# Ant-v1.net
KiCad netlist of a schematic drawn in EAGLE
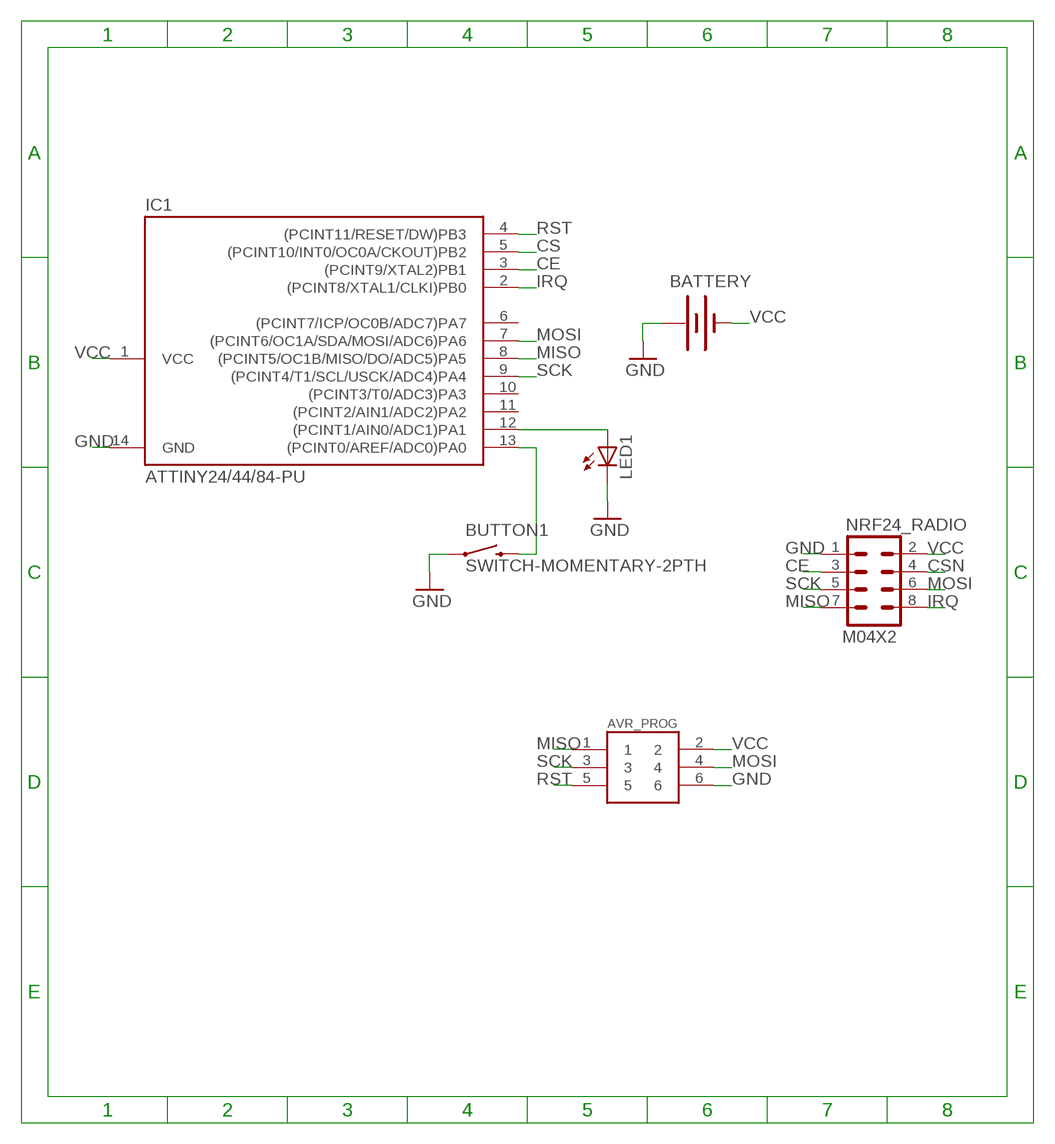
[diagram p0: schematic, sheet 1]

(export (version "E")
  (design (tool "Eeschema 10.0.6"))
  (components
    (comp (ref "AVR_PROG")
      (value "M03X2")
      (footprint "eagle-import:2X3-SHROUDED")
      (libsource (lib "eagle-import") (part "M03X2"))
    )
    (comp (ref "BATTERY")
      (value "BATTERY20PTH")
      (footprint "eagle-import:BATTCOM_20MM_PTH")
      (libsource (lib "eagle-import") (part "BATTERY20PTH"))
    )
    (comp (ref "BUTTON1")
      (value "SWITCH-MOMENTARY-2PTH")
      (footprint "eagle-import:TACTILE-PTH")
      (libsource (lib "eagle-import") (part "SWITCH-MOMENTARY-2PTH"))
    )
    (comp (ref "IC1")
      (value "ATTINY24/44/84-PU")
      (footprint "eagle-import:DIL14")
      (libsource (lib "eagle-import") (part "ATTINY24/44/84-PU"))
    )
    (comp (ref "LED1")
      (value "LED3MM")
      (footprint "eagle-import:LED3MM")
      (libsource (lib "eagle-import") (part "LED3MM"))
    )
    (comp (ref "NRF24_RADIO")
      (value "M04X2")
      (footprint "eagle-import:2X4")
      (libsource (lib "eagle-import") (part "M04X2"))
    )
  )
  (nets
    (net (code "1") (name "/CE") (class "Default")
      (node (ref "IC1") (pin "3") (pinfunction "(PCINT9/XTAL2)PB1_3") (pintype "bidirectional"))
      (node (ref "NRF24_RADIO") (pin "3") (pinfunction "3_3") (pintype "passive"))
    )
    (net (code "2") (name "/CS") (class "Default")
      (node (ref "IC1") (pin "5") (pinfunction "(PCINT10/INT0/OC0A/CKOUT)PB2_5") (pintype "bidirectional"))
    )
    (net (code "3") (name "/CSN") (class "Default")
      (node (ref "NRF24_RADIO") (pin "4") (pinfunction "4_4") (pintype "passive"))
    )
    (net (code "4") (name "/IRQ") (class "Default")
      (node (ref "IC1") (pin "2") (pinfunction "(PCINT8/XTAL1/CLKI)PB0_2") (pintype "bidirectional"))
      (node (ref "NRF24_RADIO") (pin "8") (pinfunction "8_8") (pintype "passive"))
    )
    (net (code "5") (name "/MISO") (class "Default")
      (node (ref "AVR_PROG") (pin "1") (pinfunction "1_1") (pintype "bidirectional"))
      (node (ref "IC1") (pin "8") (pinfunction "(PCINT5/OC1B/MISO/DO/ADC5)PA5_8") (pintype "bidirectional"))
      (node (ref "NRF24_RADIO") (pin "7") (pinfunction "7_7") (pintype "passive"))
    )
    (net (code "6") (name "/MOSI") (class "Default")
      (node (ref "AVR_PROG") (pin "4") (pinfunction "4_4") (pintype "bidirectional"))
      (node (ref "IC1") (pin "7") (pinfunction "(PCINT6/OC1A/SDA/MOSI/ADC6)PA6_7") (pintype "bidirectional"))
      (node (ref "NRF24_RADIO") (pin "6") (pinfunction "6_6") (pintype "passive"))
    )
    (net (code "7") (name "/RST") (class "Default")
      (node (ref "AVR_PROG") (pin "5") (pinfunction "5_5") (pintype "bidirectional"))
      (node (ref "IC1") (pin "4") (pinfunction "(PCINT11/RESET/DW)PB3_4") (pintype "bidirectional"))
    )
    (net (code "8") (name "/SCK") (class "Default")
      (node (ref "AVR_PROG") (pin "3") (pinfunction "3_3") (pintype "bidirectional"))
      (node (ref "IC1") (pin "9") (pinfunction "(PCINT4/T1/SCL/USCK/ADC4)PA4_9") (pintype "bidirectional"))
      (node (ref "NRF24_RADIO") (pin "5") (pinfunction "5_5") (pintype "passive"))
    )
    (net (code "9") (name "/VCC") (class "Default")
      (node (ref "AVR_PROG") (pin "2") (pinfunction "2_2") (pintype "bidirectional"))
      (node (ref "BATTERY") (pin "2") (pinfunction "-_2") (pintype "power_in"))
      (node (ref "IC1") (pin "1") (pinfunction "VCC_1") (pintype "power_in"))
      (node (ref "NRF24_RADIO") (pin "2") (pinfunction "2_2") (pintype "passive"))
    )
    (net (code "10") (name "GND") (class "Default")
      (node (ref "AVR_PROG") (pin "6") (pinfunction "6_6") (pintype "bidirectional"))
      (node (ref "BATTERY") (pin "1") (pinfunction "+_1") (pintype "power_in"))
      (node (ref "BUTTON1") (pin "1") (pinfunction "1_1") (pintype "passive"))
      (node (ref "IC1") (pin "14") (pinfunction "GND_14") (pintype "power_in"))
      (node (ref "LED1") (pin "K") (pinfunction "C_K") (pintype "passive"))
      (node (ref "NRF24_RADIO") (pin "1") (pinfunction "1_1") (pintype "passive"))
    )
    (net (code "11") (name "Net-(BUTTON1-2)") (class "Default")
      (node (ref "BUTTON1") (pin "3") (pinfunction "2_3") (pintype "passive"))
      (node (ref "IC1") (pin "13") (pinfunction "(PCINT0/AREF/ADC0)PA0_13") (pintype "bidirectional"))
    )
    (net (code "12") (name "Net-(IC1-(PCINT1{slash}AIN0{slash}ADC1)PA1)") (class "Default")
      (node (ref "IC1") (pin "12") (pinfunction "(PCINT1/AIN0/ADC1)PA1_12") (pintype "bidirectional"))
      (node (ref "LED1") (pin "A") (pinfunction "A_A") (pintype "passive"))
    )
    (net (code "13") (name "unconnected-(IC1-(PCINT2{slash}AIN1{slash}ADC2)PA2-Pad11)") (class "Default")
      (node (ref "IC1") (pin "11") (pinfunction "(PCINT2/AIN1/ADC2)PA2_11") (pintype "bidirectional"))
    )
    (net (code "14") (name "unconnected-(IC1-(PCINT3{slash}T0{slash}ADC3)PA3-Pad10)") (class "Default")
      (node (ref "IC1") (pin "10") (pinfunction "(PCINT3/T0/ADC3)PA3_10") (pintype "bidirectional"))
    )
    (net (code "15") (name "unconnected-(IC1-(PCINT7{slash}ICP{slash}OC0B{slash}ADC7)PA7-Pad6)") (class "Default")
      (node (ref "IC1") (pin "6") (pinfunction "(PCINT7/ICP/OC0B/ADC7)PA7_6") (pintype "bidirectional"))
    )
  )
)
